# fire_warning.net
KiCad netlist of a schematic drawn in Altium Designer
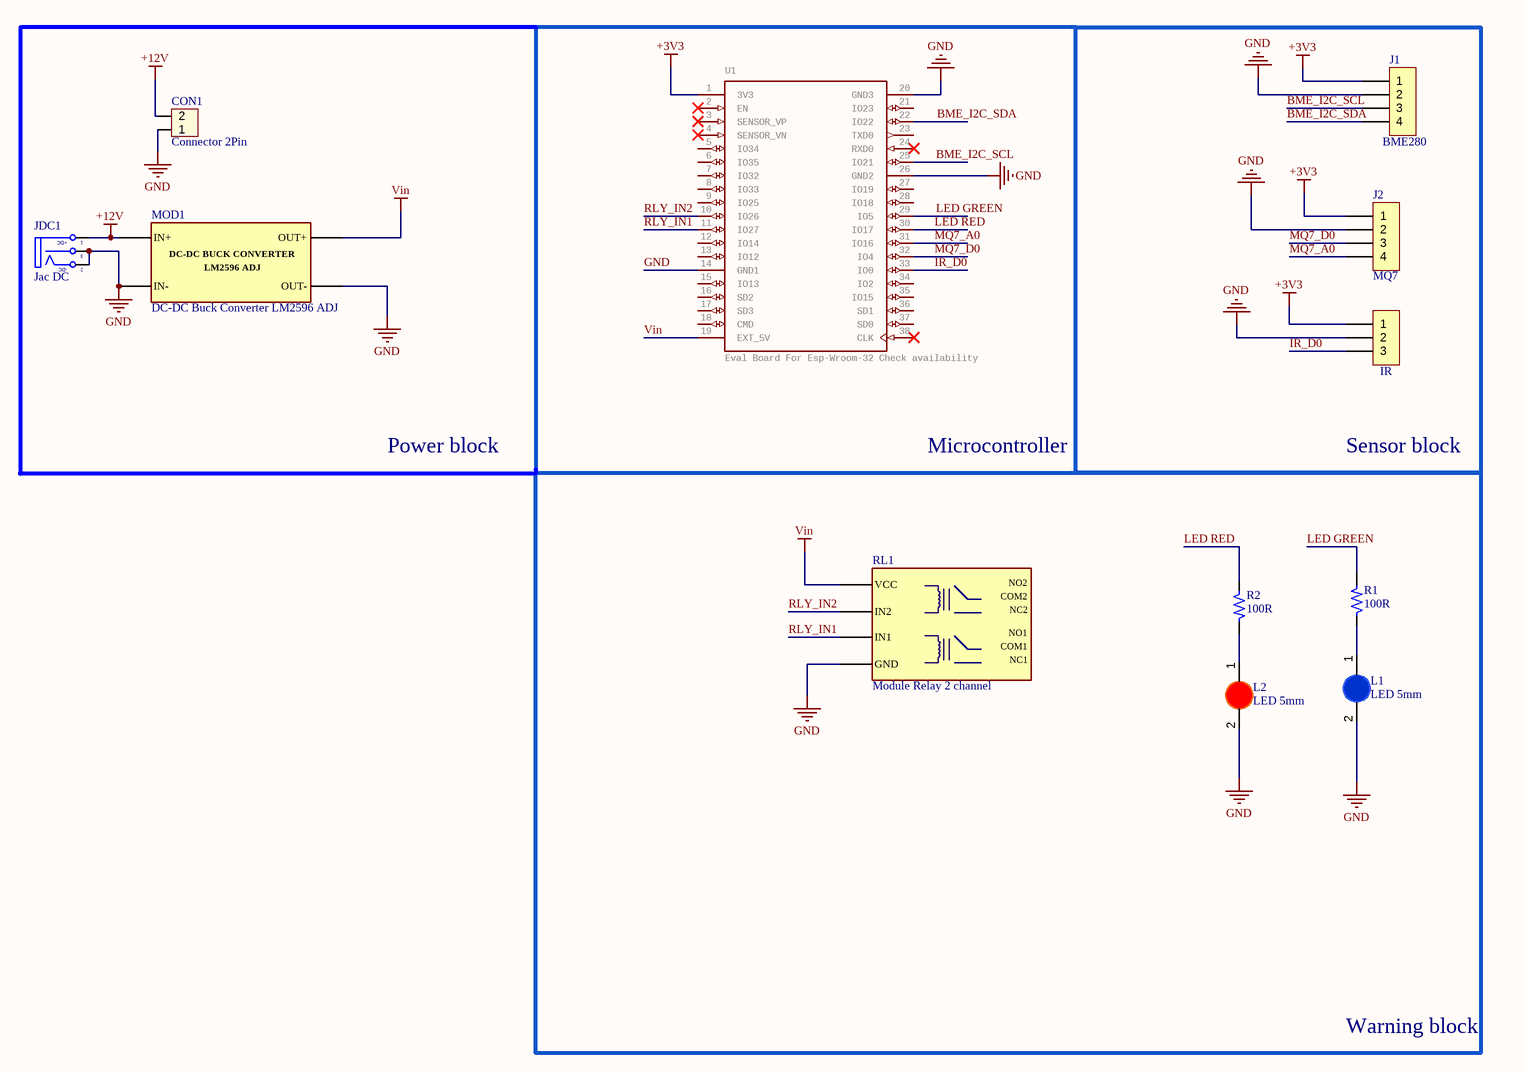
[diagram p0: fire_warning.SchDoc]

(export (version "E")
  (design (tool "Eeschema 10.0.6"))
  (components
    (comp (ref "CON1")
      (value "Connector 2Pin")
      (footprint "AD_PcbLib:Connector 2 Pin")
      (libsource (lib "AD_Lib") (part "Connector 2Pin"))
    )
    (comp (ref "J1")
      (value "BME280")
      (footprint "AD_PcbLib:XH2.54M-4")
      (description "Pitch 2.54mm")
      (libsource (lib "AD_Lib") (part "CON 4-Pin"))
    )
    (comp (ref "J2")
      (value "MQ7")
      (footprint "AD_PcbLib:XH2.54M-4")
      (description "Pitch 2.54mm")
      (libsource (lib "AD_Lib") (part "CON 4-Pin"))
    )
    (comp (ref "J3")
      (value "IR")
      (footprint "AD_PcbLib:XH2.54M-3")
      (libsource (lib "AD_Lib") (part "CON 3-Pin"))
    )
    (comp (ref "JDC1")
      (value "Jac DC")
      (footprint "AD_PcbLib:DC-IN")
      (description "Jac DC input")
      (libsource (lib "AD_Lib") (part "DCIN"))
    )
    (comp (ref "L1")
      (value "LED 5mm")
      (footprint "LED-5MM-BLUE")
      (description "Cắm")
      (libsource (lib "Altium_Lib_by_KhueNguyenCreator") (part "LED 5mm Xanh Duong"))
    )
    (comp (ref "L2")
      (value "LED 5mm")
      (footprint "LED-5MM-RED")
      (description "Cắm")
      (libsource (lib "Altium_Lib_by_KhueNguyenCreator") (part "LED 5mm Do"))
    )
    (comp (ref "MOD1")
      (value "DC-DC Buck Converter LM2596 ADJ")
      (footprint "AD_PcbLib:Module DC-DC Buck Converter LM2596")
      (description "Input: 3-30V, Output:1.5-30V. I_out = 3A (max). Dimensions: 45x20x14mm")
      (libsource (lib "AD_Lib") (part "MOD-DC-DC_Buck_LM2596_3A"))
    )
    (comp (ref "R1")
      (value "100R")
      (footprint "AD_PcbLib:Res 1/4W")
      (description "Resistor")
      (libsource (lib "AD_Lib") (part "Res"))
    )
    (comp (ref "R2")
      (value "100R")
      (footprint "AD_PcbLib:Res 1/4W")
      (description "Resistor")
      (libsource (lib "AD_Lib") (part "Res"))
    )
    (comp (ref "RL1")
      (value "Module Relay 2 channel")
      (footprint "AD_PcbLib:RLY 2 Channel")
      (description "Output: 10A/30VDC, 10A/250VAC")
      (libsource (lib "AD_Lib") (part "RLY2_5V_80mA"))
    )
    (comp (ref "U1")
      (value "Eval Board For Esp-Wroom-32 Check availability")
      (footprint "MODULE_ESP32-DEVKITC-32D")
      (fields (field (name "MP") "ESP32-DEVKITC-32D") (field (name "MF") "Espressif Systems"))
      (libsource (lib "Module") (part "ESP32-DEVKITC-32D"))
    )
  )
  (nets
    (net (code "1") (name "+3V3") (class "Default")
      (node (ref "J1") (pin "1") (pinfunction "1_1") (pintype "passive"))
      (node (ref "J2") (pin "1") (pinfunction "1_1") (pintype "passive"))
      (node (ref "J3") (pin "1") (pinfunction "1_1") (pintype "passive"))
      (node (ref "U1") (pin "1") (pinfunction "3V3_1") (pintype "power_in"))
    )
    (net (code "2") (name "+12V") (class "Default")
      (node (ref "CON1") (pin "2") (pinfunction "2_2") (pintype "passive"))
      (node (ref "JDC1") (pin "1") (pinfunction "T_1") (pintype "passive"))
      (node (ref "MOD1") (pin "1") (pinfunction "IN+_1") (pintype "passive"))
    )
    (net (code "3") (name "/BME_I2C_SCL") (class "Default")
      (node (ref "J1") (pin "3") (pinfunction "3_3") (pintype "passive"))
      (node (ref "U1") (pin "25") (pinfunction "IO21_25") (pintype "bidirectional"))
    )
    (net (code "4") (name "/BME_I2C_SDA") (class "Default")
      (node (ref "J1") (pin "4") (pinfunction "4_4") (pintype "passive"))
      (node (ref "U1") (pin "22") (pinfunction "IO22_22") (pintype "bidirectional"))
    )
    (net (code "5") (name "/IR_D0") (class "Default")
      (node (ref "J3") (pin "3") (pinfunction "3_3") (pintype "passive"))
      (node (ref "U1") (pin "33") (pinfunction "IO0_33") (pintype "bidirectional"))
    )
    (net (code "6") (name "/LED GREEN") (class "Default")
      (node (ref "R1") (pin "2") (pinfunction "2_2") (pintype "passive"))
      (node (ref "U1") (pin "29") (pinfunction "IO5_29") (pintype "bidirectional"))
    )
    (net (code "7") (name "/LED RED") (class "Default")
      (node (ref "R2") (pin "1") (pinfunction "1_1") (pintype "passive"))
      (node (ref "U1") (pin "30") (pinfunction "IO17_30") (pintype "bidirectional"))
    )
    (net (code "8") (name "/MQ7_A0") (class "Default")
      (node (ref "J2") (pin "4") (pinfunction "4_4") (pintype "passive"))
      (node (ref "U1") (pin "31") (pinfunction "IO16_31") (pintype "bidirectional"))
    )
    (net (code "9") (name "/MQ7_D0") (class "Default")
      (node (ref "J2") (pin "3") (pinfunction "3_3") (pintype "passive"))
      (node (ref "U1") (pin "32") (pinfunction "IO4_32") (pintype "bidirectional"))
    )
    (net (code "10") (name "/RLY_IN1") (class "Default")
      (node (ref "RL1") (pin "3") (pinfunction "IN1_3") (pintype "passive"))
      (node (ref "U1") (pin "11") (pinfunction "IO27_11") (pintype "bidirectional"))
    )
    (net (code "11") (name "/RLY_IN2") (class "Default")
      (node (ref "RL1") (pin "2") (pinfunction "IN2_2") (pintype "passive"))
      (node (ref "U1") (pin "10") (pinfunction "IO26_10") (pintype "bidirectional"))
    )
    (net (code "12") (name "GND") (class "Default")
      (node (ref "CON1") (pin "1") (pinfunction "1_1") (pintype "passive"))
      (node (ref "J1") (pin "2") (pinfunction "2_2") (pintype "passive"))
      (node (ref "J2") (pin "2") (pinfunction "2_2") (pintype "passive"))
      (node (ref "J3") (pin "2") (pinfunction "2_2") (pintype "passive"))
      (node (ref "JDC1") (pin "2") (pinfunction "TN_2") (pintype "passive"))
      (node (ref "JDC1") (pin "3") (pinfunction "S_3") (pintype "power_in"))
      (node (ref "L1") (pin "2") (pinfunction "K_2") (pintype "passive"))
      (node (ref "L2") (pin "2") (pinfunction "K_2") (pintype "passive"))
      (node (ref "MOD1") (pin "2") (pinfunction "IN-_2") (pintype "passive"))
      (node (ref "MOD1") (pin "4") (pinfunction "OUT-_4") (pintype "passive"))
      (node (ref "RL1") (pin "4") (pinfunction "GND_4") (pintype "passive"))
      (node (ref "U1") (pin "14") (pinfunction "GND1_14") (pintype "power_in"))
      (node (ref "U1") (pin "20") (pinfunction "GND3_20") (pintype "power_in"))
      (node (ref "U1") (pin "26") (pinfunction "GND2_26") (pintype "power_in"))
    )
    (net (code "13") (name "Net-(L1-A)") (class "Default")
      (node (ref "L1") (pin "1") (pinfunction "A_1") (pintype "passive"))
      (node (ref "R1") (pin "1") (pinfunction "1_1") (pintype "passive"))
    )
    (net (code "14") (name "Net-(L2-A)") (class "Default")
      (node (ref "L2") (pin "1") (pinfunction "A_1") (pintype "passive"))
      (node (ref "R2") (pin "2") (pinfunction "2_2") (pintype "passive"))
    )
    (net (code "15") (name "Vin") (class "Default")
      (node (ref "MOD1") (pin "3") (pinfunction "OUT+_3") (pintype "passive"))
      (node (ref "RL1") (pin "1") (pinfunction "VCC_1") (pintype "passive"))
      (node (ref "U1") (pin "19") (pinfunction "EXT_5V_19") (pintype "power_in"))
    )
    (net (code "16") (name "unconnected-(U1-CLK-Pad38)") (class "Default")
      (node (ref "U1") (pin "38") (pinfunction "CLK_38") (pintype "input+no_connect"))
    )
    (net (code "17") (name "unconnected-(U1-CMD-Pad18)") (class "Default")
      (node (ref "U1") (pin "18") (pinfunction "CMD_18") (pintype "bidirectional"))
    )
    (net (code "18") (name "unconnected-(U1-EN-Pad2)") (class "Default")
      (node (ref "U1") (pin "2") (pinfunction "EN_2") (pintype "input+no_connect"))
    )
    (net (code "19") (name "unconnected-(U1-IO2-Pad34)") (class "Default")
      (node (ref "U1") (pin "34") (pinfunction "IO2_34") (pintype "bidirectional"))
    )
    (net (code "20") (name "unconnected-(U1-IO12-Pad13)") (class "Default")
      (node (ref "U1") (pin "13") (pinfunction "IO12_13") (pintype "bidirectional"))
    )
    (net (code "21") (name "unconnected-(U1-IO13-Pad15)") (class "Default")
      (node (ref "U1") (pin "15") (pinfunction "IO13_15") (pintype "bidirectional"))
    )
    (net (code "22") (name "unconnected-(U1-IO14-Pad12)") (class "Default")
      (node (ref "U1") (pin "12") (pinfunction "IO14_12") (pintype "bidirectional"))
    )
    (net (code "23") (name "unconnected-(U1-IO15-Pad35)") (class "Default")
      (node (ref "U1") (pin "35") (pinfunction "IO15_35") (pintype "bidirectional"))
    )
    (net (code "24") (name "unconnected-(U1-IO18-Pad28)") (class "Default")
      (node (ref "U1") (pin "28") (pinfunction "IO18_28") (pintype "bidirectional"))
    )
    (net (code "25") (name "unconnected-(U1-IO19-Pad27)") (class "Default")
      (node (ref "U1") (pin "27") (pinfunction "IO19_27") (pintype "bidirectional"))
    )
    (net (code "26") (name "unconnected-(U1-IO23-Pad21)") (class "Default")
      (node (ref "U1") (pin "21") (pinfunction "IO23_21") (pintype "bidirectional"))
    )
    (net (code "27") (name "unconnected-(U1-IO25-Pad9)") (class "Default")
      (node (ref "U1") (pin "9") (pinfunction "IO25_9") (pintype "bidirectional"))
    )
    (net (code "28") (name "unconnected-(U1-IO32-Pad7)") (class "Default")
      (node (ref "U1") (pin "7") (pinfunction "IO32_7") (pintype "bidirectional"))
    )
    (net (code "29") (name "unconnected-(U1-IO33-Pad8)") (class "Default")
      (node (ref "U1") (pin "8") (pinfunction "IO33_8") (pintype "bidirectional"))
    )
    (net (code "30") (name "unconnected-(U1-IO34-Pad5)") (class "Default")
      (node (ref "U1") (pin "5") (pinfunction "IO34_5") (pintype "bidirectional"))
    )
    (net (code "31") (name "unconnected-(U1-IO35-Pad6)") (class "Default")
      (node (ref "U1") (pin "6") (pinfunction "IO35_6") (pintype "bidirectional"))
    )
    (net (code "32") (name "unconnected-(U1-RXD0-Pad24)") (class "Default")
      (node (ref "U1") (pin "24") (pinfunction "RXD0_24") (pintype "input+no_connect"))
    )
    (net (code "33") (name "unconnected-(U1-SD0-Pad37)") (class "Default")
      (node (ref "U1") (pin "37") (pinfunction "SD0_37") (pintype "bidirectional"))
    )
    (net (code "34") (name "unconnected-(U1-SD1-Pad36)") (class "Default")
      (node (ref "U1") (pin "36") (pinfunction "SD1_36") (pintype "bidirectional"))
    )
    (net (code "35") (name "unconnected-(U1-SD2-Pad16)") (class "Default")
      (node (ref "U1") (pin "16") (pinfunction "SD2_16") (pintype "bidirectional"))
    )
    (net (code "36") (name "unconnected-(U1-SD3-Pad17)") (class "Default")
      (node (ref "U1") (pin "17") (pinfunction "SD3_17") (pintype "bidirectional"))
    )
    (net (code "37") (name "unconnected-(U1-SENSOR_VN-Pad4)") (class "Default")
      (node (ref "U1") (pin "4") (pinfunction "SENSOR_VN_4") (pintype "input+no_connect"))
    )
    (net (code "38") (name "unconnected-(U1-SENSOR_VP-Pad3)") (class "Default")
      (node (ref "U1") (pin "3") (pinfunction "SENSOR_VP_3") (pintype "input+no_connect"))
    )
    (net (code "39") (name "unconnected-(U1-TXD0-Pad23)") (class "Default")
      (node (ref "U1") (pin "23") (pinfunction "TXD0_23") (pintype "output"))
    )
  )
)
